# button_board_v0_3.net
KiCad netlist of a schematic drawn in EAGLE
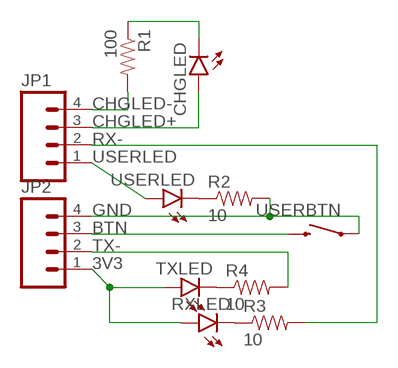
[diagram p0: schematic, sheet 1]

(export (version "E")
  (design (tool "Eeschema 10.0.6"))
  (components
    (comp (ref "CHGLED")
      (value "LED-FKIT-1206")
      (footprint "eagle-import:FKIT-LED-1206")
      (libsource (lib "eagle-import") (part "LED-FKIT-1206"))
    )
    (comp (ref "JP1")
      (value "M04PTH")
      (footprint "eagle-import:1X04")
      (libsource (lib "eagle-import") (part "M04PTH"))
    )
    (comp (ref "JP2")
      (value "M04PTH")
      (footprint "eagle-import:1X04")
      (libsource (lib "eagle-import") (part "M04PTH"))
    )
    (comp (ref "R1")
      (value "100")
      (footprint "eagle-import:0603-RES")
      (libsource (lib "eagle-import") (part "RESISTOR0603-RES"))
    )
    (comp (ref "R2")
      (value "10")
      (footprint "eagle-import:0603-RES")
      (libsource (lib "eagle-import") (part "RESISTOR0603-RES"))
    )
    (comp (ref "R3")
      (value "10")
      (footprint "eagle-import:0603-RES")
      (libsource (lib "eagle-import") (part "RESISTOR0603-RES"))
    )
    (comp (ref "R4")
      (value "10")
      (footprint "eagle-import:0603-RES")
      (libsource (lib "eagle-import") (part "RESISTOR0603-RES"))
    )
    (comp (ref "RXLED")
      (value "LED-FKIT-1206")
      (footprint "eagle-import:FKIT-LED-1206")
      (libsource (lib "eagle-import") (part "LED-FKIT-1206"))
    )
    (comp (ref "TXLED")
      (value "LED-FKIT-1206")
      (footprint "eagle-import:FKIT-LED-1206")
      (libsource (lib "eagle-import") (part "LED-FKIT-1206"))
    )
    (comp (ref "USERBTN")
      (value "SWITCH-MOMENTARY-2PCB_MOUNTSMD_OMRON_B3S_100X")
      (footprint "eagle-import:TACTILE_SWITCH_LARGE")
      (libsource (lib "eagle-import") (part "SWITCH-MOMENTARY-2SMD_OMRON_B3S_100XPCB_MOUNT"))
    )
    (comp (ref "USERLED")
      (value "LED-FKIT-1206")
      (footprint "eagle-import:FKIT-LED-1206")
      (libsource (lib "eagle-import") (part "LED-FKIT-1206"))
    )
  )
  (nets
    (net (code "1") (name "/3V3") (class "Default")
      (node (ref "JP2") (pin "1") (pinfunction "1_1") (pintype "passive"))
      (node (ref "RXLED") (pin "A") (pinfunction "A_A") (pintype "passive"))
      (node (ref "TXLED") (pin "A") (pinfunction "A_A") (pintype "passive"))
    )
    (net (code "2") (name "/BTN") (class "Default")
      (node (ref "JP2") (pin "3") (pinfunction "3_3") (pintype "passive"))
      (node (ref "USERBTN") (pin "3") (pinfunction "2_3") (pintype "passive"))
      (node (ref "USERBTN") (pin "4") (pinfunction "2_4") (pintype "passive"))
    )
    (net (code "3") (name "/CHGLED+") (class "Default")
      (node (ref "CHGLED") (pin "A") (pinfunction "A_A") (pintype "passive"))
      (node (ref "JP1") (pin "3") (pinfunction "3_3") (pintype "passive"))
    )
    (net (code "4") (name "/CHGLED-") (class "Default")
      (node (ref "JP1") (pin "4") (pinfunction "4_4") (pintype "passive"))
      (node (ref "R1") (pin "2") (pinfunction "2_2") (pintype "passive"))
    )
    (net (code "5") (name "/GND") (class "Default")
      (node (ref "JP2") (pin "4") (pinfunction "4_4") (pintype "passive"))
      (node (ref "R2") (pin "2") (pinfunction "2_2") (pintype "passive"))
      (node (ref "USERBTN") (pin "1") (pinfunction "1_1") (pintype "passive"))
      (node (ref "USERBTN") (pin "2") (pinfunction "1_2") (pintype "passive"))
    )
    (net (code "6") (name "/RX-") (class "Default")
      (node (ref "JP1") (pin "2") (pinfunction "2_2") (pintype "passive"))
      (node (ref "R3") (pin "2") (pinfunction "2_2") (pintype "passive"))
    )
    (net (code "7") (name "/TX-") (class "Default")
      (node (ref "JP2") (pin "2") (pinfunction "2_2") (pintype "passive"))
      (node (ref "R4") (pin "2") (pinfunction "2_2") (pintype "passive"))
    )
    (net (code "8") (name "/USERLED") (class "Default")
      (node (ref "JP1") (pin "1") (pinfunction "1_1") (pintype "passive"))
      (node (ref "USERLED") (pin "A") (pinfunction "A_A") (pintype "passive"))
    )
    (net (code "9") (name "Net-(CHGLED-PadC)") (class "Default")
      (node (ref "CHGLED") (pin "C") (pinfunction "C_C") (pintype "passive"))
      (node (ref "R1") (pin "1") (pinfunction "1_1") (pintype "passive"))
    )
    (net (code "10") (name "Net-(R2-Pad1)") (class "Default")
      (node (ref "R2") (pin "1") (pinfunction "1_1") (pintype "passive"))
      (node (ref "USERLED") (pin "C") (pinfunction "C_C") (pintype "passive"))
    )
    (net (code "11") (name "Net-(R3-Pad1)") (class "Default")
      (node (ref "R3") (pin "1") (pinfunction "1_1") (pintype "passive"))
      (node (ref "RXLED") (pin "C") (pinfunction "C_C") (pintype "passive"))
    )
    (net (code "12") (name "Net-(R4-Pad1)") (class "Default")
      (node (ref "R4") (pin "1") (pinfunction "1_1") (pintype "passive"))
      (node (ref "TXLED") (pin "C") (pinfunction "C_C") (pintype "passive"))
    )
  )
)
